# 2364_Multi-ROM_Rev3.net
KiCad netlist of a schematic drawn in EAGLE
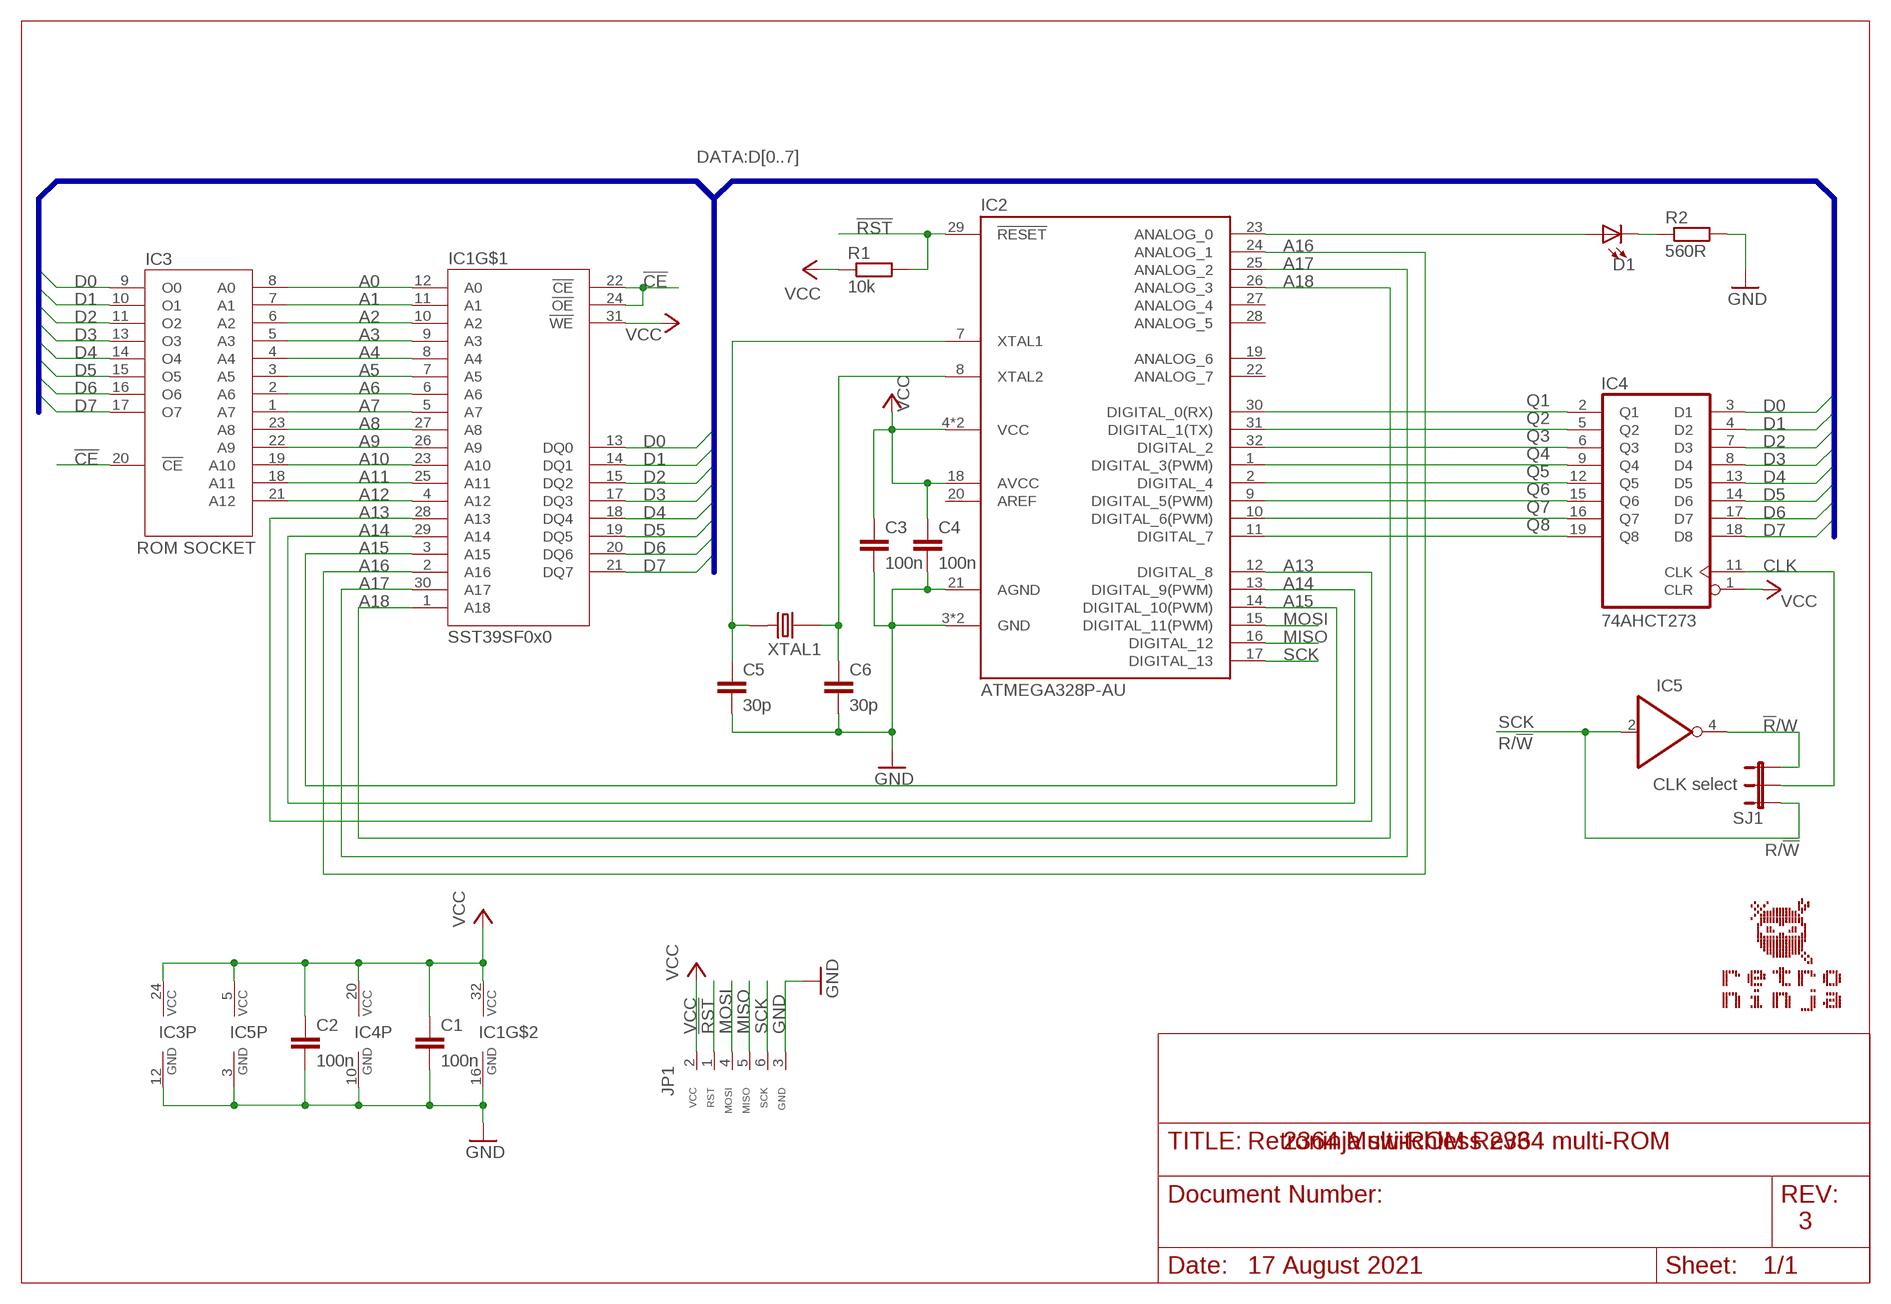
[diagram p0: schematic, sheet 1]

(export (version "E")
  (design (tool "Eeschema 10.0.6"))
  (components
    (comp (ref "C1")
      (value "100n")
      (footprint "eagle-import:C0805")
      (libsource (lib "eagle-import") (part "C-EUC0805"))
    )
    (comp (ref "C2")
      (value "100n")
      (footprint "eagle-import:C0805")
      (libsource (lib "eagle-import") (part "C-EUC0805"))
    )
    (comp (ref "C3")
      (value "100n")
      (footprint "eagle-import:C0805")
      (libsource (lib "eagle-import") (part "C-EUC0805"))
    )
    (comp (ref "C4")
      (value "100n")
      (footprint "eagle-import:C0805")
      (libsource (lib "eagle-import") (part "C-EUC0805"))
    )
    (comp (ref "C5")
      (value "30p")
      (footprint "eagle-import:C0805")
      (libsource (lib "eagle-import") (part "C-EUC0805"))
    )
    (comp (ref "C6")
      (value "30p")
      (footprint "eagle-import:C0805")
      (libsource (lib "eagle-import") (part "C-EUC0805"))
    )
    (comp (ref "D1")
      (value "LED_0805")
      (footprint "eagle-import:LED0805")
      (libsource (lib "eagle-import") (part "LED_0805"))
    )
    (comp (ref "IC1")
      (value "SST39SF0x0")
      (footprint "eagle-import:PLCC32_SHORT")
      (libsource (lib "eagle-import") (part "SST39XX040_PLCC_SHORT"))
    )
    (comp (ref "IC2")
      (value "ATMEGA328P-AU")
      (footprint "eagle-import:TQFP32")
      (libsource (lib "eagle-import") (part "ARDUINO_168_328_TQFP"))
    )
    (comp (ref "IC3")
      (value "ROM SOCKET")
      (footprint "eagle-import:DIL24-6_DOWNPINS")
      (libsource (lib "eagle-import") (part "2364_DOWNPINS"))
    )
    (comp (ref "IC4")
      (value "74AHCT273")
      (footprint "eagle-import:SO20")
      (libsource (lib "eagle-import") (part "74273NS"))
    )
    (comp (ref "IC5")
      (value "741G04_SOT23")
      (footprint "eagle-import:SOT23-5")
      (libsource (lib "eagle-import") (part "741G04_SOT23"))
    )
    (comp (ref "JP1")
      (value "ICSP_CONNECTOR_TL866_RIGHT2")
      (footprint "eagle-import:HEADER_1X6_RIGHT")
      (libsource (lib "eagle-import") (part "ICSP_CONNECTOR_TL866_RIGHT2"))
    )
    (comp (ref "R1")
      (value "10k")
      (footprint "eagle-import:R0805")
      (libsource (lib "eagle-import") (part "R-EU_R0805"))
    )
    (comp (ref "R2")
      (value "560R")
      (footprint "eagle-import:R0805")
      (libsource (lib "eagle-import") (part "R-EU_R0805"))
    )
    (comp (ref "SJ1")
      (value "JUMPER-3SJ")
      (footprint "eagle-import:SJ-3")
      (libsource (lib "eagle-import") (part "JUMPER-3SJ"))
    )
    (comp (ref "XTAL1")
      (value "CRYSTAL")
      (footprint "eagle-import:CRYSTAL_SMD-2_7X4X2.3")
      (libsource (lib "eagle-import") (part "CRYSTAL"))
    )
  )
  (nets
    (net (code "9") (name "/A0") (class "Default")
      (node (ref "IC1") (pin "12") (pinfunction "A0_12") (pintype "input"))
      (node (ref "IC3") (pin "8") (pinfunction "A0_8") (pintype "input"))
    )
    (net (code "10") (name "/A1") (class "Default")
      (node (ref "IC1") (pin "11") (pinfunction "A1_11") (pintype "input"))
      (node (ref "IC3") (pin "7") (pinfunction "A1_7") (pintype "input"))
    )
    (net (code "11") (name "/A2") (class "Default")
      (node (ref "IC1") (pin "10") (pinfunction "A2_10") (pintype "input"))
      (node (ref "IC3") (pin "6") (pinfunction "A2_6") (pintype "input"))
    )
    (net (code "12") (name "/A3") (class "Default")
      (node (ref "IC1") (pin "9") (pinfunction "A3_9") (pintype "input"))
      (node (ref "IC3") (pin "5") (pinfunction "A3_5") (pintype "input"))
    )
    (net (code "13") (name "/A4") (class "Default")
      (node (ref "IC1") (pin "8") (pinfunction "A4_8") (pintype "input"))
      (node (ref "IC3") (pin "4") (pinfunction "A4_4") (pintype "input"))
    )
    (net (code "14") (name "/A5") (class "Default")
      (node (ref "IC1") (pin "7") (pinfunction "A5_7") (pintype "input"))
      (node (ref "IC3") (pin "3") (pinfunction "A5_3") (pintype "input"))
    )
    (net (code "15") (name "/A6") (class "Default")
      (node (ref "IC1") (pin "6") (pinfunction "A6_6") (pintype "input"))
      (node (ref "IC3") (pin "2") (pinfunction "A6_2") (pintype "input"))
    )
    (net (code "16") (name "/A7") (class "Default")
      (node (ref "IC1") (pin "5") (pinfunction "A7_5") (pintype "input"))
      (node (ref "IC3") (pin "1") (pinfunction "A7_1") (pintype "input"))
    )
    (net (code "17") (name "/A8") (class "Default")
      (node (ref "IC1") (pin "27") (pinfunction "A8_27") (pintype "input"))
      (node (ref "IC3") (pin "23") (pinfunction "A8_23") (pintype "input"))
    )
    (net (code "18") (name "/A9") (class "Default")
      (node (ref "IC1") (pin "26") (pinfunction "A9_26") (pintype "input"))
      (node (ref "IC3") (pin "22") (pinfunction "A9_22") (pintype "input"))
    )
    (net (code "19") (name "/A10") (class "Default")
      (node (ref "IC1") (pin "23") (pinfunction "A10_23") (pintype "input"))
      (node (ref "IC3") (pin "19") (pinfunction "A10_19") (pintype "input"))
    )
    (net (code "20") (name "/A11") (class "Default")
      (node (ref "IC1") (pin "25") (pinfunction "A11_25") (pintype "input"))
      (node (ref "IC3") (pin "18") (pinfunction "A11_18") (pintype "input"))
    )
    (net (code "21") (name "/A12") (class "Default")
      (node (ref "IC1") (pin "4") (pinfunction "A12_4") (pintype "input"))
      (node (ref "IC3") (pin "21") (pinfunction "A12_21") (pintype "input"))
    )
    (net (code "22") (name "/A13") (class "Default")
      (node (ref "IC1") (pin "28") (pinfunction "A13_28") (pintype "input"))
      (node (ref "IC2") (pin "12") (pinfunction "DIGITAL_8_12") (pintype "bidirectional"))
    )
    (net (code "23") (name "/A14") (class "Default")
      (node (ref "IC1") (pin "29") (pinfunction "A14_29") (pintype "input"))
      (node (ref "IC2") (pin "13") (pinfunction "DIGITAL_9(PWM)_13") (pintype "bidirectional"))
    )
    (net (code "24") (name "/A15") (class "Default")
      (node (ref "IC1") (pin "3") (pinfunction "A15_3") (pintype "input"))
      (node (ref "IC2") (pin "14") (pinfunction "DIGITAL_10(PWM)_14") (pintype "bidirectional"))
    )
    (net (code "25") (name "/A16") (class "Default")
      (node (ref "IC1") (pin "2") (pinfunction "A16_2") (pintype "input"))
      (node (ref "IC2") (pin "24") (pinfunction "ANALOG_1_24") (pintype "bidirectional"))
    )
    (net (code "26") (name "/A17") (class "Default")
      (node (ref "IC1") (pin "30") (pinfunction "A17_30") (pintype "input"))
      (node (ref "IC2") (pin "25") (pinfunction "ANALOG_2_25") (pintype "bidirectional"))
    )
    (net (code "27") (name "/A18") (class "Default")
      (node (ref "IC1") (pin "1") (pinfunction "A18_1") (pintype "input"))
      (node (ref "IC2") (pin "26") (pinfunction "ANALOG_3_26") (pintype "bidirectional"))
    )
    (net (code "28") (name "/CLK") (class "Default")
      (node (ref "IC4") (pin "11") (pinfunction "CLK_11") (pintype "input"))
      (node (ref "SJ1") (pin "2") (pinfunction "2_2") (pintype "passive"))
    )
    (net (code "29") (name "/D0") (class "Default")
      (node (ref "IC1") (pin "13") (pinfunction "DQ0_13") (pintype "bidirectional"))
      (node (ref "IC3") (pin "9") (pinfunction "O0_9") (pintype "tri_state"))
      (node (ref "IC4") (pin "3") (pinfunction "D1_3") (pintype "input"))
    )
    (net (code "30") (name "/D1") (class "Default")
      (node (ref "IC1") (pin "14") (pinfunction "DQ1_14") (pintype "bidirectional"))
      (node (ref "IC3") (pin "10") (pinfunction "O1_10") (pintype "tri_state"))
      (node (ref "IC4") (pin "4") (pinfunction "D2_4") (pintype "input"))
    )
    (net (code "31") (name "/D2") (class "Default")
      (node (ref "IC1") (pin "15") (pinfunction "DQ2_15") (pintype "bidirectional"))
      (node (ref "IC3") (pin "11") (pinfunction "O2_11") (pintype "tri_state"))
      (node (ref "IC4") (pin "7") (pinfunction "D3_7") (pintype "input"))
    )
    (net (code "32") (name "/D3") (class "Default")
      (node (ref "IC1") (pin "17") (pinfunction "DQ3_17") (pintype "bidirectional"))
      (node (ref "IC3") (pin "13") (pinfunction "O3_13") (pintype "tri_state"))
      (node (ref "IC4") (pin "8") (pinfunction "D4_8") (pintype "input"))
    )
    (net (code "33") (name "/D4") (class "Default")
      (node (ref "IC1") (pin "18") (pinfunction "DQ4_18") (pintype "bidirectional"))
      (node (ref "IC3") (pin "14") (pinfunction "O4_14") (pintype "tri_state"))
      (node (ref "IC4") (pin "13") (pinfunction "D5_13") (pintype "input"))
    )
    (net (code "34") (name "/D5") (class "Default")
      (node (ref "IC1") (pin "19") (pinfunction "DQ5_19") (pintype "bidirectional"))
      (node (ref "IC3") (pin "15") (pinfunction "O5_15") (pintype "tri_state"))
      (node (ref "IC4") (pin "14") (pinfunction "D6_14") (pintype "input"))
    )
    (net (code "35") (name "/D6") (class "Default")
      (node (ref "IC1") (pin "20") (pinfunction "DQ6_20") (pintype "bidirectional"))
      (node (ref "IC3") (pin "16") (pinfunction "O6_16") (pintype "tri_state"))
      (node (ref "IC4") (pin "17") (pinfunction "D7_17") (pintype "input"))
    )
    (net (code "36") (name "/D7") (class "Default")
      (node (ref "IC1") (pin "21") (pinfunction "DQ7_21") (pintype "bidirectional"))
      (node (ref "IC3") (pin "17") (pinfunction "O7_17") (pintype "tri_state"))
      (node (ref "IC4") (pin "18") (pinfunction "D8_18") (pintype "input"))
    )
    (net (code "38") (name "/MISO") (class "Default")
      (node (ref "IC2") (pin "16") (pinfunction "DIGITAL_12_16") (pintype "bidirectional"))
      (node (ref "JP1") (pin "5") (pinfunction "MISO_5") (pintype "output"))
    )
    (net (code "39") (name "/MOSI") (class "Default")
      (node (ref "IC2") (pin "15") (pinfunction "DIGITAL_11(PWM)_15") (pintype "bidirectional"))
      (node (ref "JP1") (pin "4") (pinfunction "MOSI_4") (pintype "input"))
    )
    (net (code "40") (name "/Q1") (class "Default")
      (node (ref "IC2") (pin "30") (pinfunction "DIGITAL_0(RX)_30") (pintype "bidirectional"))
      (node (ref "IC4") (pin "2") (pinfunction "Q1_2") (pintype "output"))
    )
    (net (code "41") (name "/Q2") (class "Default")
      (node (ref "IC2") (pin "31") (pinfunction "DIGITAL_1(TX)_31") (pintype "bidirectional"))
      (node (ref "IC4") (pin "5") (pinfunction "Q2_5") (pintype "output"))
    )
    (net (code "42") (name "/Q3") (class "Default")
      (node (ref "IC2") (pin "32") (pinfunction "DIGITAL_2_32") (pintype "bidirectional"))
      (node (ref "IC4") (pin "6") (pinfunction "Q3_6") (pintype "output"))
    )
    (net (code "43") (name "/Q4") (class "Default")
      (node (ref "IC2") (pin "1") (pinfunction "DIGITAL_3(PWM)_1") (pintype "bidirectional"))
      (node (ref "IC4") (pin "9") (pinfunction "Q4_9") (pintype "output"))
    )
    (net (code "44") (name "/Q5") (class "Default")
      (node (ref "IC2") (pin "2") (pinfunction "DIGITAL_4_2") (pintype "bidirectional"))
      (node (ref "IC4") (pin "12") (pinfunction "Q5_12") (pintype "output"))
    )
    (net (code "45") (name "/Q6") (class "Default")
      (node (ref "IC2") (pin "9") (pinfunction "DIGITAL_5(PWM)_9") (pintype "bidirectional"))
      (node (ref "IC4") (pin "15") (pinfunction "Q6_15") (pintype "output"))
    )
    (net (code "46") (name "/Q7") (class "Default")
      (node (ref "IC2") (pin "10") (pinfunction "DIGITAL_6(PWM)_10") (pintype "bidirectional"))
      (node (ref "IC4") (pin "16") (pinfunction "Q7_16") (pintype "output"))
    )
    (net (code "47") (name "/Q8") (class "Default")
      (node (ref "IC2") (pin "11") (pinfunction "DIGITAL_7_11") (pintype "bidirectional"))
      (node (ref "IC4") (pin "19") (pinfunction "Q8_19") (pintype "output"))
    )
    (net (code "48") (name "/SCK") (class "Default")
      (node (ref "IC2") (pin "17") (pinfunction "DIGITAL_13_17") (pintype "bidirectional"))
      (node (ref "IC5") (pin "2") (pinfunction "I_2") (pintype "input"))
      (node (ref "JP1") (pin "6") (pinfunction "SCK_6") (pintype "input"))
      (node (ref "SJ1") (pin "1") (pinfunction "1_1") (pintype "passive"))
    )
    (net (code "49") (name "/~{CE}") (class "Default")
      (node (ref "IC1") (pin "22") (pinfunction "~{CE}_22") (pintype "input"))
      (node (ref "IC1") (pin "24") (pinfunction "~{OE}_24") (pintype "input"))
      (node (ref "IC3") (pin "20") (pinfunction "~{CE}_20") (pintype "input"))
    )
    (net (code "50") (name "/~{RST}") (class "Default")
      (node (ref "IC2") (pin "29") (pinfunction "~{RESET}_29") (pintype "bidirectional"))
      (node (ref "JP1") (pin "1") (pinfunction "RST_1") (pintype "input"))
      (node (ref "R1") (pin "2") (pinfunction "2_2") (pintype "passive"))
    )
    (net (code "51") (name "/~{R}{slash}W") (class "Default")
      (node (ref "IC5") (pin "4") (pinfunction "O_4") (pintype "output"))
      (node (ref "SJ1") (pin "3") (pinfunction "3_3") (pintype "passive"))
    )
    (net (code "52") (name "GND") (class "Default")
      (node (ref "C1") (pin "2") (pinfunction "2_2") (pintype "passive"))
      (node (ref "C2") (pin "2") (pinfunction "2_2") (pintype "passive"))
      (node (ref "C3") (pin "2") (pinfunction "2_2") (pintype "passive"))
      (node (ref "C4") (pin "2") (pinfunction "2_2") (pintype "passive"))
      (node (ref "C5") (pin "2") (pinfunction "2_2") (pintype "passive"))
      (node (ref "C6") (pin "2") (pinfunction "2_2") (pintype "passive"))
      (node (ref "IC1") (pin "16") (pinfunction "GND_16") (pintype "power_in"))
      (node (ref "IC2") (pin "21") (pinfunction "AGND_21") (pintype "passive"))
      (node (ref "IC2") (pin "3") (pinfunction "GND_3") (pintype "passive"))
      (node (ref "IC2") (pin "5") (pinfunction "GND_5") (pintype "passive"))
      (node (ref "IC3") (pin "12") (pinfunction "GND_12") (pintype "power_in"))
      (node (ref "IC4") (pin "10") (pinfunction "GND_10") (pintype "power_in"))
      (node (ref "IC5") (pin "3") (pinfunction "GND_3") (pintype "power_in"))
      (node (ref "JP1") (pin "3") (pinfunction "GND_3") (pintype "power_in"))
      (node (ref "R2") (pin "2") (pinfunction "2_2") (pintype "passive"))
    )
    (net (code "53") (name "Net-(D1-PadC)") (class "Default")
      (node (ref "D1") (pin "C") (pinfunction "C_C") (pintype "passive"))
      (node (ref "R2") (pin "1") (pinfunction "1_1") (pintype "passive"))
    )
    (net (code "54") (name "Net-(IC2-ANALOG_0)") (class "Default")
      (node (ref "D1") (pin "A") (pinfunction "A_A") (pintype "passive"))
      (node (ref "IC2") (pin "23") (pinfunction "ANALOG_0_23") (pintype "bidirectional"))
    )
    (net (code "55") (name "Net-(IC2-XTAL1)") (class "Default")
      (node (ref "C5") (pin "1") (pinfunction "1_1") (pintype "passive"))
      (node (ref "IC2") (pin "7") (pinfunction "XTAL1_7") (pintype "bidirectional"))
      (node (ref "XTAL1") (pin "2") (pinfunction "2_2") (pintype "passive"))
    )
    (net (code "56") (name "Net-(IC2-XTAL2)") (class "Default")
      (node (ref "C6") (pin "1") (pinfunction "1_1") (pintype "passive"))
      (node (ref "IC2") (pin "8") (pinfunction "XTAL2_8") (pintype "bidirectional"))
      (node (ref "XTAL1") (pin "1") (pinfunction "1_1") (pintype "passive"))
    )
    (net (code "57") (name "VCC") (class "Default")
      (node (ref "C1") (pin "1") (pinfunction "1_1") (pintype "passive"))
      (node (ref "C2") (pin "1") (pinfunction "1_1") (pintype "passive"))
      (node (ref "C3") (pin "1") (pinfunction "1_1") (pintype "passive"))
      (node (ref "C4") (pin "1") (pinfunction "1_1") (pintype "passive"))
      (node (ref "IC1") (pin "31") (pinfunction "~{WE}_31") (pintype "input"))
      (node (ref "IC1") (pin "32") (pinfunction "VCC_32") (pintype "power_in"))
      (node (ref "IC2") (pin "18") (pinfunction "AVCC_18") (pintype "passive"))
      (node (ref "IC2") (pin "4") (pinfunction "VCC_4") (pintype "passive"))
      (node (ref "IC2") (pin "6") (pinfunction "VCC_6") (pintype "passive"))
      (node (ref "IC3") (pin "24") (pinfunction "VCC_24") (pintype "power_in"))
      (node (ref "IC4") (pin "1") (pinfunction "CLR_1") (pintype "input"))
      (node (ref "IC4") (pin "20") (pinfunction "VCC_20") (pintype "power_in"))
      (node (ref "IC5") (pin "5") (pinfunction "VCC_5") (pintype "power_in"))
      (node (ref "JP1") (pin "2") (pinfunction "VCC_2") (pintype "power_in"))
      (node (ref "R1") (pin "1") (pinfunction "1_1") (pintype "passive"))
    )
    (net (code "58") (name "unconnected-(IC2-ANALOG_4-Pad27)") (class "Default")
      (node (ref "IC2") (pin "27") (pinfunction "ANALOG_4_27") (pintype "bidirectional"))
    )
    (net (code "59") (name "unconnected-(IC2-ANALOG_5-Pad28)") (class "Default")
      (node (ref "IC2") (pin "28") (pinfunction "ANALOG_5_28") (pintype "bidirectional"))
    )
    (net (code "60") (name "unconnected-(IC2-ANALOG_6-Pad19)") (class "Default")
      (node (ref "IC2") (pin "19") (pinfunction "ANALOG_6_19") (pintype "bidirectional"))
    )
    (net (code "61") (name "unconnected-(IC2-ANALOG_7-Pad22)") (class "Default")
      (node (ref "IC2") (pin "22") (pinfunction "ANALOG_7_22") (pintype "bidirectional"))
    )
    (net (code "62") (name "unconnected-(IC2-AREF-Pad20)") (class "Default")
      (node (ref "IC2") (pin "20") (pinfunction "AREF_20") (pintype "passive"))
    )
  )
)
